# Sheet_2.net
KiCad netlist of a schematic drawn in Altium Designer
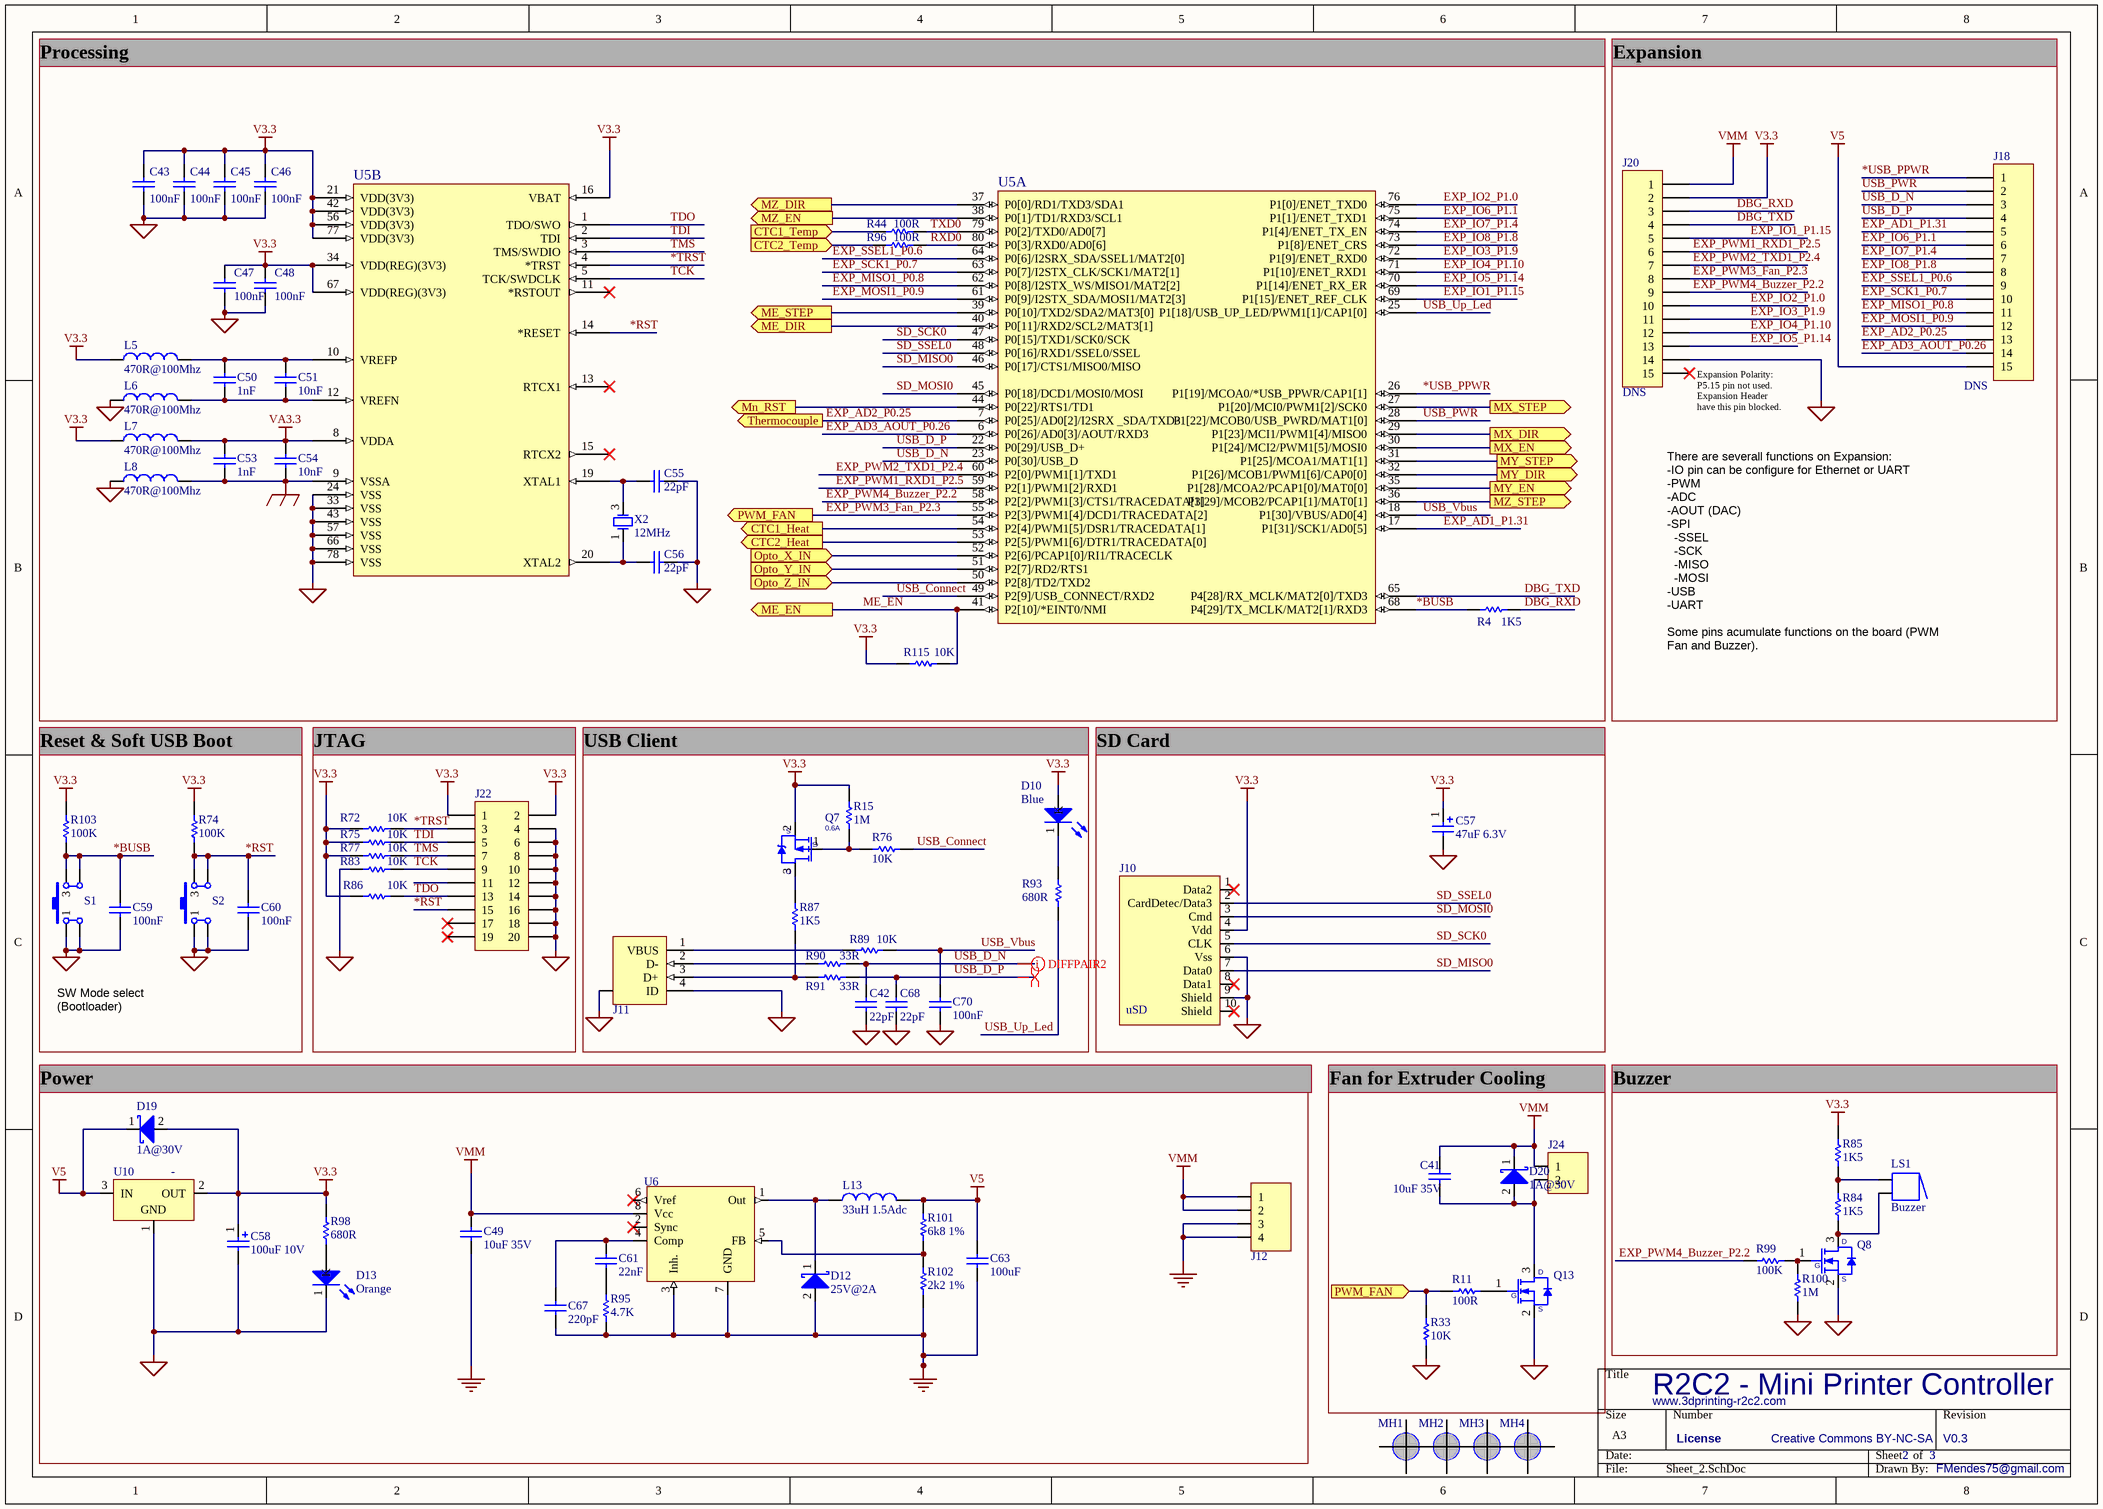
[diagram p0: Sheet_2.SchDoc]

(export (version "E")
  (design (tool "Eeschema 10.0.6"))
  (components
    (comp (ref "C41")
      (value "10uF 35V")
      (footprint "CAPC3216M")
      (description "CAP CER 10UF 35V Y5V 1206")
      (fields (field (name "MANUFACTURER") "Taiyo Yuden"))
      (libsource (lib "HB_DB_Components") (part "Cap Non Pol"))
    )
    (comp (ref "C42")
      (value "22pF")
      (footprint "CAPC1608M")
      (description "CAP CER 22PF 50V 5% NP0 0603")
      (fields (field (name "MANUFACTURER") "TDK"))
      (libsource (lib "HB_DB_Components") (part "Cap Non Pol"))
    )
    (comp (ref "C43")
      (value "100nF")
      (footprint "CAPC1608M")
      (description "CAP CER 0.1UF 50V Y5V 0603")
      (fields (field (name "MANUFACTURER") "Yageo"))
      (libsource (lib "HB_DB_Components") (part "Cap Non Pol"))
    )
    (comp (ref "C44")
      (value "100nF")
      (footprint "CAPC1608M")
      (description "CAP CER 0.1UF 50V Y5V 0603")
      (fields (field (name "MANUFACTURER") "Yageo"))
      (libsource (lib "HB_DB_Components") (part "Cap Non Pol"))
    )
    (comp (ref "C45")
      (value "100nF")
      (footprint "CAPC1608M")
      (description "CAP CER 0.1UF 50V Y5V 0603")
      (fields (field (name "MANUFACTURER") "Yageo"))
      (libsource (lib "HB_DB_Components") (part "Cap Non Pol"))
    )
    (comp (ref "C46")
      (value "100nF")
      (footprint "CAPC1608M")
      (description "CAP CER 0.1UF 50V Y5V 0603")
      (fields (field (name "MANUFACTURER") "Yageo"))
      (libsource (lib "HB_DB_Components") (part "Cap Non Pol"))
    )
    (comp (ref "C47")
      (value "100nF")
      (footprint "CAPC1608M")
      (description "CAP CER 0.1UF 50V Y5V 0603")
      (fields (field (name "MANUFACTURER") "Yageo"))
      (libsource (lib "HB_DB_Components") (part "Cap Non Pol"))
    )
    (comp (ref "C48")
      (value "100nF")
      (footprint "CAPC1608M")
      (description "CAP CER 0.1UF 50V Y5V 0603")
      (fields (field (name "MANUFACTURER") "Yageo"))
      (libsource (lib "HB_DB_Components") (part "Cap Non Pol"))
    )
    (comp (ref "C49")
      (value "10uF 35V")
      (footprint "CAPC3216M")
      (description "CAP CER 10UF 35V Y5V 1206")
      (fields (field (name "MANUFACTURER") "Taiyo Yuden"))
      (libsource (lib "HB_DB_Components") (part "Cap Non Pol"))
    )
    (comp (ref "C50")
      (value "1nF")
      (footprint "CAPC1608M")
      (description "CAP CER 1000PF 50V 10% X7R 0603")
      (fields (field (name "MANUFACTURER") "TDK"))
      (libsource (lib "HB_DB_Components") (part "Cap Non Pol"))
    )
    (comp (ref "C51")
      (value "10nF")
      (footprint "CAPC1608M")
      (description "CAP CER 10000PF 50V 10% X7R 0603")
      (fields (field (name "MANUFACTURER") "TDK"))
      (libsource (lib "HB_DB_Components") (part "Cap Non Pol"))
    )
    (comp (ref "C53")
      (value "1nF")
      (footprint "CAPC1608M")
      (description "CAP CER 1000PF 50V 10% X7R 0603")
      (fields (field (name "MANUFACTURER") "TDK"))
      (libsource (lib "HB_DB_Components") (part "Cap Non Pol"))
    )
    (comp (ref "C54")
      (value "10nF")
      (footprint "CAPC1608M")
      (description "CAP CER 10000PF 50V 10% X7R 0603")
      (fields (field (name "MANUFACTURER") "TDK"))
      (libsource (lib "HB_DB_Components") (part "Cap Non Pol"))
    )
    (comp (ref "C55")
      (value "22pF")
      (footprint "CAPC1608M")
      (description "CAP CER 22PF 50V 5% NP0 0603")
      (fields (field (name "MANUFACTURER") "TDK"))
      (libsource (lib "HB_DB_Components") (part "Cap Non Pol"))
    )
    (comp (ref "C56")
      (value "22pF")
      (footprint "CAPC1608M")
      (description "CAP CER 22PF 50V 5% NP0 0603")
      (fields (field (name "MANUFACTURER") "TDK"))
      (libsource (lib "HB_DB_Components") (part "Cap Non Pol"))
    )
    (comp (ref "C57")
      (value "47uF 6.3V")
      (footprint "Tant_nichicon_B")
      (description "CAP TANT 47UF 6.3V 10% 1411")
      (fields (field (name "MANUFACTURER") "Nichicon"))
      (libsource (lib "HB_DB_Components") (part "Cap Pol"))
    )
    (comp (ref "C58")
      (value "100uF 10V")
      (footprint "CAPAE6666X54M")
      (description "CAP ALUM 100UF 16V 20% SMD")
      (fields (field (name "MANUFACTURER") "Nichicon"))
      (libsource (lib "HB_DB_Components") (part "Cap Pol"))
    )
    (comp (ref "C59")
      (value "100nF")
      (footprint "CAPC1608M")
      (description "CAP CER 0.1UF 50V Y5V 0603")
      (fields (field (name "MANUFACTURER") "Yageo"))
      (libsource (lib "HB_DB_Components") (part "Cap Non Pol"))
    )
    (comp (ref "C60")
      (value "100nF")
      (footprint "CAPC1608M")
      (description "CAP CER 0.1UF 50V Y5V 0603")
      (fields (field (name "MANUFACTURER") "Yageo"))
      (libsource (lib "HB_DB_Components") (part "Cap Non Pol"))
    )
    (comp (ref "C61")
      (value "22nF")
      (footprint "CAPC1608M")
      (description "CAP CER 0.022UF 50V 20% X7R 0603")
      (fields (field (name "MANUFACTURER") "TDK"))
      (libsource (lib "HB_DB_Components") (part "Cap Non Pol"))
    )
    (comp (ref "C63")
      (value "100uF")
      (footprint "CAPC3216M")
      (description "CAP CER 100UF 10V 20% X5R 1206")
      (fields (field (name "MANUFACTURER") "TDK"))
      (libsource (lib "HB_DB_Components") (part "Cap Non Pol"))
    )
    (comp (ref "C67")
      (value "220pF")
      (footprint "CAPC1608M")
      (description "CAP CER 220PF 50V 5% NP0 0603")
      (fields (field (name "MANUFACTURER") "TDK"))
      (libsource (lib "HB_DB_Components") (part "Cap Non Pol"))
    )
    (comp (ref "C68")
      (value "22pF")
      (footprint "CAPC1608M")
      (description "CAP CER 22PF 50V 5% NP0 0603")
      (fields (field (name "MANUFACTURER") "TDK"))
      (libsource (lib "HB_DB_Components") (part "Cap Non Pol"))
    )
    (comp (ref "C70")
      (value "100nF")
      (footprint "CAPC1608M")
      (description "CAP CER 0.1UF 50V Y5V 0603")
      (fields (field (name "MANUFACTURER") "Yageo"))
      (libsource (lib "HB_DB_Components") (part "Cap Non Pol"))
    )
    (comp (ref "D10")
      (value "Blue")
      (footprint "LEDM_3216X12M")
      (description "LED BLUE CLEAR 1206 REV MT SMD")
      (fields (field (name "MANUFACTURER") "Lite-On Inc"))
      (libsource (lib "HB_DB_Components") (part "LED"))
    )
    (comp (ref "D12")
      (value "25V@2A")
      (footprint "SMB")
      (description "DIODE SCHOTTKY 25V 2A SMB")
      (fields (field (name "MANUFACTURER") "STMicroelectronics"))
      (libsource (lib "HB_DB_Components") (part "D Schottky"))
    )
    (comp (ref "D13")
      (value "Orange")
      (footprint "LEDM_3216X12M")
      (description "LED 3.2X1.6MM 601NM ORN CLR SMD")
      (fields (field (name "MANUFACTURER") "OSRAM"))
      (libsource (lib "HB_DB_Components") (part "LED"))
    )
    (comp (ref "D19")
      (value "1A@30V")
      (footprint "SOD323")
      (description "DIODE SCHOTTKY 30V 1A SOD323F")
      (fields (field (name "MANUFACTURER") "NXP"))
      (libsource (lib "HB_DB_Components") (part "D Schottky"))
    )
    (comp (ref "D20")
      (value "1A@30V")
      (footprint "SOD323")
      (description "DIODE SCHOTTKY 30V 1A SOD323F")
      (fields (field (name "MANUFACTURER") "NXP"))
      (libsource (lib "HB_DB_Components") (part "D Schottky"))
    )
    (comp (ref "J10")
      (value "uSD")
      (footprint "3M_2900")
      (description "CONN MINI MICRO-SD 8PIN PCB GOLD")
      (fields (field (name "MANUFACTURER") "Amphenol"))
      (libsource (lib "HB_DB_Components") (part "Con uSD"))
    )
    (comp (ref "J11")
      (value "micro-usb")
      (footprint "USB_47589-001")
      (description "CONN RCPT MICRO USB AB R/A SMD")
      (fields (field (name "MANUFACTURER") "Molex Inc"))
      (libsource (lib "HB") (part "Con 4 USB"))
    )
    (comp (ref "J12")
      (value "~")
      (footprint "TE_SCREW_282841-4")
      (description "Con 4")
      (fields (field (name "MANUFACTURER") "TE"))
      (libsource (lib "HB_DB_Components") (part "Con 4"))
    )
    (comp (ref "J18")
      (value "~")
      (footprint "HDR1X15")
      (description "15 SIL VERT PIN HDR")
      (fields (field (name "POPULATE") "DNS") (field (name "MANUFACTURER") "Harwin Inc"))
      (libsource (lib "HB_DB_Components") (part "Con 15"))
    )
    (comp (ref "J20")
      (value "~")
      (footprint "HDR1X15")
      (description "15 SIL VERT PIN HDR")
      (fields (field (name "POPULATE") "DNS") (field (name "MANUFACTURER") "Harwin Inc"))
      (libsource (lib "") (part "Con 15_1"))
    )
    (comp (ref "J22")
      (value "~")
      (footprint "HDR2X10")
      (description "Headers & Wire Housings 2 X 10 SHROUDED HDR")
      (fields (field (name "MANUFACTURER") "Molex"))
      (libsource (lib "HB_DB_Components") (part "Con 10X2"))
    )
    (comp (ref "J24")
      (value "-")
      (footprint "MOLEX_22-29-2021")
      (description "CONN HEADER 2POS .100 VERT GOLD")
      (fields (field (name "MANUFACTURER") "Molex"))
      (libsource (lib "HB_DB_Components") (part "Con 2"))
    )
    (comp (ref "L5")
      (value "470R@100Mhz")
      (footprint "INDC1608M")
      (description "FERRITE CHIP 470 OHM 1000MA 0603")
      (fields (field (name "MANUFACTURER") "MURATA"))
      (libsource (lib "HB_DB_Components") (part "Ind"))
    )
    (comp (ref "L6")
      (value "470R@100Mhz")
      (footprint "INDC1608M")
      (description "FERRITE CHIP 470 OHM 1000MA 0603")
      (fields (field (name "MANUFACTURER") "MURATA"))
      (libsource (lib "HB_DB_Components") (part "Ind"))
    )
    (comp (ref "L7")
      (value "470R@100Mhz")
      (footprint "INDC1608M")
      (description "FERRITE CHIP 470 OHM 1000MA 0603")
      (fields (field (name "MANUFACTURER") "MURATA"))
      (libsource (lib "HB_DB_Components") (part "Ind"))
    )
    (comp (ref "L8")
      (value "470R@100Mhz")
      (footprint "INDC1608M")
      (description "FERRITE CHIP 470 OHM 1000MA 0603")
      (fields (field (name "MANUFACTURER") "MURATA"))
      (libsource (lib "HB_DB_Components") (part "Ind"))
    )
    (comp (ref "L13")
      (value "33uH 1.5Adc")
      (footprint "INDP6x6")
      (description "INDUCTOR 33UH 1.4A 20% SMD")
      (fields (field (name "MANUFACTURER") "Taiyo Yuden"))
      (libsource (lib "HB_DB_Components") (part "Ind"))
    )
    (comp (ref "LS1")
      (value "Buzzer")
      (footprint "TDK_PS1240")
      (description "BUZZER PIEZO 4KHZ 12.2MM PC MNT")
      (fields (field (name "MANUFACTURER") "TDK"))
      (libsource (lib "HB_DB_Components") (part "Buzzer"))
    )
    (comp (ref "MH1")
      (value "-")
      (footprint "MH_M3")
      (description "MH")
      (libsource (lib "HB_DB_Components") (part "MH"))
    )
    (comp (ref "MH2")
      (value "-")
      (footprint "MH_M3")
      (description "MH")
      (libsource (lib "HB_DB_Components") (part "MH"))
    )
    (comp (ref "MH3")
      (value "-")
      (footprint "MH_M3")
      (description "MH")
      (libsource (lib "HB_DB_Components") (part "MH"))
    )
    (comp (ref "MH4")
      (value "-")
      (footprint "MH_M3")
      (description "MH")
      (libsource (lib "HB_DB_Components") (part "MH"))
    )
    (comp (ref "Q7")
      (value "0.6A")
      (footprint "SOT23-3M")
      (description "MOSFET P-CH 30V 760MA SOT-23")
      (fields (field (name "MANUFACTURER") "International Rectifier"))
      (libsource (lib "HB_DB_Components") (part "MOS-P"))
    )
    (comp (ref "Q8")
      (value "~")
      (footprint "SOT323-3AM")
      (description "MOSFET N-CH SGL 60V SOT-323")
      (fields (field (name "MANUFACTURER") "NXP"))
      (libsource (lib "HB_DB_Components") (part "Q MOSFET-N"))
    )
    (comp (ref "Q13")
      (value "~")
      (footprint "SOT323-3AM")
      (description "MOSFET N-CH SGL 60V SOT-323")
      (fields (field (name "MANUFACTURER") "NXP"))
      (libsource (lib "HB_DB_Components") (part "Q MOSFET-N"))
    )
    (comp (ref "R4")
      (value "1K5")
      (footprint "RESC1608M")
      (description "RES 1.5K OHM 1/10W 5% 0603")
      (fields (field (name "MANUFACTURER") "Stackpole Electronics Inc"))
      (libsource (lib "HB_DB_Components") (part "Res"))
    )
    (comp (ref "R11")
      (value "100R")
      (footprint "RESC1608M")
      (description "RES 100 OHM 1/10W 5% 0603")
      (fields (field (name "MANUFACTURER") "Stackpole Electronics Inc"))
      (libsource (lib "HB_DB_Components") (part "Res"))
    )
    (comp (ref "R15")
      (value "1M")
      (footprint "RESC1608M")
      (description "RES 1M OHM 1/10W 1% 0603")
      (fields (field (name "MANUFACTURER") "Stackpole Electronics Inc"))
      (libsource (lib "HB_DB_Components") (part "Res"))
    )
    (comp (ref "R33")
      (value "10K")
      (footprint "RESC1608M")
      (description "RES 10K OHM 1/10W 5% 0603 SMD")
      (fields (field (name "MANUFACTURER") "Yageo"))
      (libsource (lib "HB_DB_Components") (part "Res"))
    )
    (comp (ref "R44")
      (value "100R")
      (footprint "RESC1608M")
      (description "RES 100 OHM 1/10W 5% 0603")
      (fields (field (name "MANUFACTURER") "Stackpole Electronics Inc"))
      (libsource (lib "HB_DB_Components") (part "Res"))
    )
    (comp (ref "R72")
      (value "10K")
      (footprint "RESC1608M")
      (description "RES 10K OHM 1/10W 5% 0603 SMD")
      (fields (field (name "MANUFACTURER") "Yageo"))
      (libsource (lib "HB_DB_Components") (part "Res"))
    )
    (comp (ref "R74")
      (value "100K")
      (footprint "RESC1608M")
      (description "RES 100K OHM 1/10W 5% 0603 SMD")
      (fields (field (name "MANUFACTURER") "Yageo"))
      (libsource (lib "HB_DB_Components") (part "Res"))
    )
    (comp (ref "R75")
      (value "10K")
      (footprint "RESC1608M")
      (description "RES 10K OHM 1/10W 5% 0603 SMD")
      (fields (field (name "MANUFACTURER") "Yageo"))
      (libsource (lib "HB_DB_Components") (part "Res"))
    )
    (comp (ref "R76")
      (value "10K")
      (footprint "RESC1608M")
      (description "RES 10K OHM 1/10W 5% 0603 SMD")
      (fields (field (name "MANUFACTURER") "Yageo"))
      (libsource (lib "HB_DB_Components") (part "Res"))
    )
    (comp (ref "R77")
      (value "10K")
      (footprint "RESC1608M")
      (description "RES 10K OHM 1/10W 5% 0603 SMD")
      (fields (field (name "MANUFACTURER") "Yageo"))
      (libsource (lib "HB_DB_Components") (part "Res"))
    )
    (comp (ref "R83")
      (value "10K")
      (footprint "RESC1608M")
      (description "RES 10K OHM 1/10W 5% 0603 SMD")
      (fields (field (name "MANUFACTURER") "Yageo"))
      (libsource (lib "HB_DB_Components") (part "Res"))
    )
    (comp (ref "R84")
      (value "1K5")
      (footprint "RESC1608M")
      (description "RES 1.5K OHM 1/10W 5% 0603")
      (fields (field (name "MANUFACTURER") "Stackpole Electronics Inc"))
      (libsource (lib "HB_DB_Components") (part "Res"))
    )
    (comp (ref "R85")
      (value "1K5")
      (footprint "RESC1608M")
      (description "RES 1.5K OHM 1/10W 5% 0603")
      (fields (field (name "MANUFACTURER") "Stackpole Electronics Inc"))
      (libsource (lib "HB_DB_Components") (part "Res"))
    )
    (comp (ref "R86")
      (value "10K")
      (footprint "RESC1608M")
      (description "RES 10K OHM 1/10W 5% 0603 SMD")
      (fields (field (name "MANUFACTURER") "Yageo"))
      (libsource (lib "HB_DB_Components") (part "Res"))
    )
    (comp (ref "R87")
      (value "1K5")
      (footprint "RESC1608M")
      (description "RES 1.5K OHM 1/10W 5% 0603")
      (fields (field (name "MANUFACTURER") "Stackpole Electronics Inc"))
      (libsource (lib "HB_DB_Components") (part "Res"))
    )
    (comp (ref "R89")
      (value "10K")
      (footprint "RESC1608M")
      (description "RES 10K OHM 1/10W 5% 0603 SMD")
      (fields (field (name "MANUFACTURER") "Yageo"))
      (libsource (lib "HB_DB_Components") (part "Res"))
    )
    (comp (ref "R90")
      (value "33R")
      (footprint "RESC1608M")
      (description "RES 33 OHM 1/10W 1% 0603")
      (fields (field (name "MANUFACTURER") "Stackpole Electronics Inc"))
      (libsource (lib "HB_DB_Components") (part "Res"))
    )
    (comp (ref "R91")
      (value "33R")
      (footprint "RESC1608M")
      (description "RES 33 OHM 1/10W 1% 0603")
      (fields (field (name "MANUFACTURER") "Stackpole Electronics Inc"))
      (libsource (lib "HB_DB_Components") (part "Res"))
    )
    (comp (ref "R93")
      (value "680R")
      (footprint "RESC1608M")
      (description "RES 680 OHM 1/10W 1% 0603 SMD")
      (fields (field (name "MANUFACTURER") "Panasonic"))
      (libsource (lib "HB_DB_Components") (part "Res"))
    )
    (comp (ref "R95")
      (value "4.7K")
      (footprint "CAPC1608M")
      (description "4K7")
      (fields (field (name "MANUFACTURER") "Multicomp"))
      (libsource (lib "HB_DB_Components") (part "Res"))
    )
    (comp (ref "R96")
      (value "100R")
      (footprint "RESC1608M")
      (description "RES 100 OHM 1/10W 5% 0603")
      (fields (field (name "MANUFACTURER") "Stackpole Electronics Inc"))
      (libsource (lib "HB_DB_Components") (part "Res"))
    )
    (comp (ref "R98")
      (value "680R")
      (footprint "RESC1608M")
      (description "RES 680 OHM 1/10W 1% 0603 SMD")
      (fields (field (name "MANUFACTURER") "Panasonic"))
      (libsource (lib "HB_DB_Components") (part "Res"))
    )
    (comp (ref "R99")
      (value "100K")
      (footprint "RESC1608M")
      (description "RES 100K OHM 1/10W 5% 0603 SMD")
      (fields (field (name "MANUFACTURER") "Yageo"))
      (libsource (lib "HB_DB_Components") (part "Res"))
    )
    (comp (ref "R100")
      (value "1M")
      (footprint "RESC1608M")
      (description "RES 1M OHM 1/10W 1% 0603")
      (fields (field (name "MANUFACTURER") "Stackpole Electronics Inc"))
      (libsource (lib "HB_DB_Components") (part "Res"))
    )
    (comp (ref "R101")
      (value "6k8 1%")
      (footprint "RESC1608M")
      (description "RES 6.8K OHM 1/10W 1% 0603")
      (fields (field (name "MANUFACTURER") "Stackpole Electronics Inc"))
      (libsource (lib "HB_DB_Components") (part "Res"))
    )
    (comp (ref "R102")
      (value "2k2 1%")
      (footprint "RESC1608M")
      (description "RES 2.2K OHM 1/10W .1% 0603 SMD")
      (fields (field (name "MANUFACTURER") "Panasonic"))
      (libsource (lib "HB_DB_Components") (part "Res"))
    )
    (comp (ref "R103")
      (value "100K")
      (footprint "RESC1608M")
      (description "RES 100K OHM 1/10W 5% 0603 SMD")
      (fields (field (name "MANUFACTURER") "Yageo"))
      (libsource (lib "HB_DB_Components") (part "Res"))
    )
    (comp (ref "R115")
      (value "10K")
      (footprint "RESC1608M")
      (description "RES 10K OHM 1/10W 5% 0603 SMD")
      (fields (field (name "MANUFACTURER") "Yageo"))
      (libsource (lib "HB_DB_Components") (part "Res"))
    )
    (comp (ref "S1")
      (value "SW-PB")
      (footprint "SW_FSM6JSMA")
      (description "SWITCH TACTILE SPST-NO 0.05A 12V")
      (fields (field (name "MANUFACTURER") "TE Connectivity"))
      (libsource (lib "HB_DB_Components") (part "SW-PB"))
    )
    (comp (ref "S2")
      (value "SW-PB")
      (footprint "SW_FSM6JSMA")
      (description "SWITCH TACTILE SPST-NO 0.05A 12V")
      (fields (field (name "MANUFACTURER") "TE Connectivity"))
      (libsource (lib "HB_DB_Components") (part "SW-PB"))
    )
    (comp (ref "U5")
      (value "~")
      (footprint "TSQFP50P1400X1400X160-80M")
      (description "IC ARM CORTEX MCU 512K 80-LQFP")
      (fields (field (name "MANUFACTURER") "NXP"))
      (libsource (lib "HB_DB_Components") (part "IC LPC175x"))
    )
    (comp (ref "U6")
      (value "~")
      (footprint "SOIC127P600-8M")
      (description "IC REG BUCK ADJ 1A 8SOIC")
      (fields (field (name "MANUFACTURER") "STMicroelectronics"))
      (libsource (lib "HB_DB_Components") (part "IC L5970D"))
    )
    (comp (ref "U10")
      (value "-")
      (footprint "SOT223-4M")
      (description "IC REG LDO 3.3V 0.8A SOT223")
      (fields (field (name "MANUFACTURER") "Texas Instruments"))
      (libsource (lib "HB_DB_Components") (part "IC_TLV1117-3.3"))
    )
    (comp (ref "X2")
      (value "12MHz")
      (footprint "txc_7b_12MHZ")
      (description "CRYSTAL 12.000MHZ 18PF SMD")
      (fields (field (name "MANUFACTURER") "TXC CORPORATION"))
      (libsource (lib "HB_DB_Components") (part "XTAL"))
    )
  )
  (nets
    (net (code "1") (name "/*BUSB") (class "Default")
      (node (ref "C59") (pin "2") (pinfunction "2_2") (pintype "passive"))
      (node (ref "R103") (pin "1") (pinfunction "1_1") (pintype "passive"))
      (node (ref "R4") (pin "1") (pinfunction "1_1") (pintype "passive"))
      (node (ref "S1") (pin "3") (pinfunction "3_3") (pintype "passive"))
      (node (ref "S1") (pin "4") (pinfunction "4_4") (pintype "passive"))
      (node (ref "U5") (pin "68") (pinfunction "P4[29]/TX_MCLK/MAT2[1]/RXD3_68") (pintype "bidirectional"))
    )
    (net (code "2") (name "/*RST") (class "Default")
      (node (ref "C60") (pin "2") (pinfunction "2_2") (pintype "passive"))
      (node (ref "J22") (pin "15") (pinfunction "15_15") (pintype "passive"))
      (node (ref "R74") (pin "1") (pinfunction "1_1") (pintype "passive"))
      (node (ref "S2") (pin "3") (pinfunction "3_3") (pintype "passive"))
      (node (ref "S2") (pin "4") (pinfunction "4_4") (pintype "passive"))
      (node (ref "U5") (pin "14") (pinfunction "*RESET_14") (pintype "input"))
    )
    (net (code "3") (name "/*TRST") (class "Default")
      (node (ref "J22") (pin "3") (pinfunction "3_3") (pintype "passive"))
      (node (ref "R72") (pin "2") (pinfunction "2_2") (pintype "passive"))
      (node (ref "U5") (pin "4") (pinfunction "*TRST_4") (pintype "input"))
    )
    (net (code "4") (name "/*USB_PPWR") (class "Default")
      (node (ref "J18") (pin "1") (pinfunction "1_1") (pintype "passive"))
      (node (ref "U5") (pin "26") (pinfunction "P1[19]/MCOA0/*USB_PPWR/CAP1[1]_26") (pintype "bidirectional"))
    )
    (net (code "5") (name "/CTC1_Heat") (class "Default")
      (node (ref "U5") (pin "54") (pinfunction "P2[4]/PWM1[5]/DSR1/TRACEDATA[1]_54") (pintype "bidirectional"))
    )
    (net (code "6") (name "/CTC1_Temp") (class "Default")
      (node (ref "R44") (pin "1") (pinfunction "1_1") (pintype "passive"))
    )
    (net (code "7") (name "/CTC2_Heat") (class "Default")
      (node (ref "U5") (pin "53") (pinfunction "P2[5]/PWM1[6]/DTR1/TRACEDATA[0]_53") (pintype "bidirectional"))
    )
    (net (code "8") (name "/CTC2_Temp") (class "Default")
      (node (ref "R96") (pin "1") (pinfunction "1_1") (pintype "passive"))
    )
    (net (code "9") (name "/DBG_RXD") (class "Default")
      (node (ref "J20") (pin "3") (pinfunction "3_3") (pintype "passive"))
      (node (ref "R4") (pin "2") (pinfunction "2_2") (pintype "passive"))
    )
    (net (code "10") (name "/DBG_TXD") (class "Default")
      (node (ref "J20") (pin "4") (pinfunction "4_4") (pintype "passive"))
      (node (ref "U5") (pin "65") (pinfunction "P4[28]/RX_MCLK/MAT2[0]/TXD3_65") (pintype "bidirectional"))
    )
    (net (code "11") (name "/EXP_AD1_P1.31") (class "Default")
      (node (ref "J18") (pin "5") (pinfunction "5_5") (pintype "passive"))
      (node (ref "U5") (pin "17") (pinfunction "P1[31]/SCK1/AD0[5]_17") (pintype "bidirectional"))
    )
    (net (code "12") (name "/EXP_AD2_P0.25") (class "Default")
      (node (ref "J18") (pin "13") (pinfunction "13_13") (pintype "passive"))
      (node (ref "U5") (pin "7") (pinfunction "P0[25]/AD0[2]/I2SRX__SDA/TXD3_7") (pintype "bidirectional"))
    )
    (net (code "13") (name "/EXP_AD3_AOUT_P0.26") (class "Default")
      (node (ref "J18") (pin "14") (pinfunction "14_14") (pintype "passive"))
      (node (ref "U5") (pin "6") (pinfunction "P0[26]/AD0[3]/AOUT/RXD3_6") (pintype "bidirectional"))
    )
    (net (code "14") (name "/EXP_IO1_P1.15") (class "Default")
      (node (ref "J20") (pin "5") (pinfunction "5_5") (pintype "passive"))
      (node (ref "U5") (pin "69") (pinfunction "P1[15]/ENET_REF_CLK_69") (pintype "bidirectional"))
    )
    (net (code "15") (name "/EXP_IO2_P1.0") (class "Default")
      (node (ref "J20") (pin "10") (pinfunction "10_10") (pintype "passive"))
      (node (ref "U5") (pin "76") (pinfunction "P1[0]/ENET_TXD0_76") (pintype "bidirectional"))
    )
    (net (code "16") (name "/EXP_IO3_P1.9") (class "Default")
      (node (ref "J20") (pin "11") (pinfunction "11_11") (pintype "passive"))
      (node (ref "U5") (pin "72") (pinfunction "P1[9]/ENET_RXD0_72") (pintype "bidirectional"))
    )
    (net (code "17") (name "/EXP_IO4_P1.10") (class "Default")
      (node (ref "J20") (pin "12") (pinfunction "12_12") (pintype "passive"))
      (node (ref "U5") (pin "71") (pinfunction "P1[10]/ENET_RXD1_71") (pintype "bidirectional"))
    )
    (net (code "18") (name "/EXP_IO5_P1.14") (class "Default")
      (node (ref "J20") (pin "13") (pinfunction "13_13") (pintype "passive"))
      (node (ref "U5") (pin "70") (pinfunction "P1[14]/ENET_RX_ER_70") (pintype "bidirectional"))
    )
    (net (code "19") (name "/EXP_IO6_P1.1") (class "Default")
      (node (ref "J18") (pin "6") (pinfunction "6_6") (pintype "passive"))
      (node (ref "U5") (pin "75") (pinfunction "P1[1]/ENET_TXD1_75") (pintype "bidirectional"))
    )
    (net (code "20") (name "/EXP_IO7_P1.4") (class "Default")
      (node (ref "J18") (pin "7") (pinfunction "7_7") (pintype "passive"))
      (node (ref "U5") (pin "74") (pinfunction "P1[4]/ENET_TX_EN_74") (pintype "bidirectional"))
    )
    (net (code "21") (name "/EXP_IO8_P1.8") (class "Default")
      (node (ref "J18") (pin "8") (pinfunction "8_8") (pintype "passive"))
      (node (ref "U5") (pin "73") (pinfunction "P1[8]/ENET_CRS_73") (pintype "bidirectional"))
    )
    (net (code "22") (name "/EXP_MISO1_P0.8") (class "Default")
      (node (ref "J18") (pin "11") (pinfunction "11_11") (pintype "passive"))
      (node (ref "U5") (pin "62") (pinfunction "P0[8]/I2STX_WS/MISO1/MAT2[2]_62") (pintype "bidirectional"))
    )
    (net (code "23") (name "/EXP_MOSI1_P0.9") (class "Default")
      (node (ref "J18") (pin "12") (pinfunction "12_12") (pintype "passive"))
      (node (ref "U5") (pin "61") (pinfunction "P0[9]/I2STX_SDA/MOSI1/MAT2[3]_61") (pintype "bidirectional"))
    )
    (net (code "24") (name "/EXP_PWM1_RXD1_P2.5") (class "Default")
      (node (ref "J20") (pin "6") (pinfunction "6_6") (pintype "passive"))
      (node (ref "U5") (pin "59") (pinfunction "P2[1]/PWM1[2]/RXD1_59") (pintype "bidirectional"))
    )
    (net (code "25") (name "/EXP_PWM2_TXD1_P2.4") (class "Default")
      (node (ref "J20") (pin "7") (pinfunction "7_7") (pintype "passive"))
      (node (ref "U5") (pin "60") (pinfunction "P2[0]/PWM1[1]/TXD1_60") (pintype "bidirectional"))
    )
    (net (code "26") (name "/EXP_PWM3_Fan_P2.3") (class "Default")
      (node (ref "J20") (pin "8") (pinfunction "8_8") (pintype "passive"))
      (node (ref "R11") (pin "1") (pinfunction "1_1") (pintype "passive"))
      (node (ref "R33") (pin "2") (pinfunction "2_2") (pintype "passive"))
      (node (ref "U5") (pin "55") (pinfunction "P2[3]/PWM1[4]/DCD1/TRACEDATA[2]_55") (pintype "bidirectional"))
    )
    (net (code "27") (name "/EXP_PWM4_Buzzer_P2.2") (class "Default")
      (node (ref "J20") (pin "9") (pinfunction "9_9") (pintype "passive"))
      (node (ref "R99") (pin "1") (pinfunction "1_1") (pintype "passive"))
      (node (ref "U5") (pin "58") (pinfunction "P2[2]/PWM1[3]/CTS1/TRACEDATA[3]_58") (pintype "bidirectional"))
    )
    (net (code "28") (name "/EXP_SCK1_P0.7") (class "Default")
      (node (ref "J18") (pin "10") (pinfunction "10_10") (pintype "passive"))
      (node (ref "U5") (pin "63") (pinfunction "P0[7]/I2STX_CLK/SCK1/MAT2[1]_63") (pintype "bidirectional"))
    )
    (net (code "29") (name "/EXP_SSEL1_P0.6") (class "Default")
      (node (ref "J18") (pin "9") (pinfunction "9_9") (pintype "passive"))
      (node (ref "U5") (pin "64") (pinfunction "P0[6]/I2SRX_SDA/SSEL1/MAT2[0]_64") (pintype "bidirectional"))
    )
    (net (code "30") (name "/ME_DIR") (class "Default")
      (node (ref "U5") (pin "40") (pinfunction "P0[11]/RXD2/SCL2/MAT3[1]_40") (pintype "bidirectional"))
    )
    (net (code "31") (name "/ME_EN") (class "Default")
      (node (ref "R115") (pin "2") (pinfunction "2_2") (pintype "passive"))
      (node (ref "U5") (pin "41") (pinfunction "P2[10]/*EINT0/NMI_41") (pintype "bidirectional"))
    )
    (net (code "32") (name "/ME_STEP") (class "Default")
      (node (ref "U5") (pin "39") (pinfunction "P0[10]/TXD2/SDA2/MAT3[0]_39") (pintype "bidirectional"))
    )
    (net (code "33") (name "/MX_DIR") (class "Default")
      (node (ref "U5") (pin "29") (pinfunction "P1[23]/MCI1/PWM1[4]/MISO0_29") (pintype "bidirectional"))
    )
    (net (code "34") (name "/MX_EN") (class "Default")
      (node (ref "U5") (pin "30") (pinfunction "P1[24]/MCI2/PWM1[5]/MOSI0_30") (pintype "bidirectional"))
    )
    (net (code "35") (name "/MX_STEP") (class "Default")
      (node (ref "U5") (pin "27") (pinfunction "P1[20]/MCI0/PWM1[2]/SCK0_27") (pintype "bidirectional"))
    )
    (net (code "36") (name "/MY_DIR") (class "Default")
      (node (ref "U5") (pin "32") (pinfunction "P1[26]/MCOB1/PWM1[6]/CAP0[0]_32") (pintype "bidirectional"))
    )
    (net (code "37") (name "/MY_EN") (class "Default")
      (node (ref "U5") (pin "35") (pinfunction "P1[28]/MCOA2/PCAP1[0]/MAT0[0]_35") (pintype "bidirectional"))
    )
    (net (code "38") (name "/MY_STEP") (class "Default")
      (node (ref "U5") (pin "31") (pinfunction "P1[25]/MCOA1/MAT1[1]_31") (pintype "bidirectional"))
    )
    (net (code "39") (name "/MZ_DIR") (class "Default")
      (node (ref "U5") (pin "37") (pinfunction "P0[0]/RD1/TXD3/SDA1_37") (pintype "bidirectional"))
    )
    (net (code "40") (name "/MZ_EN") (class "Default")
      (node (ref "U5") (pin "38") (pinfunction "P0[1]/TD1/RXD3/SCL1_38") (pintype "bidirectional"))
    )
    (net (code "41") (name "/MZ_STEP") (class "Default")
      (node (ref "U5") (pin "36") (pinfunction "P1[29]/MCOB2/PCAP1[1]/MAT0[1]_36") (pintype "bidirectional"))
    )
    (net (code "42") (name "/Mn_RST") (class "Default")
      (node (ref "U5") (pin "44") (pinfunction "P0[22]/RTS1/TD1_44") (pintype "bidirectional"))
    )
    (net (code "43") (name "/Opto_X_IN") (class "Default")
      (node (ref "U5") (pin "52") (pinfunction "P2[6]/PCAP1[0]/RI1/TRACECLK_52") (pintype "bidirectional"))
    )
    (net (code "44") (name "/Opto_Y_IN") (class "Default")
      (node (ref "U5") (pin "51") (pinfunction "P2[7]/RD2/RTS1_51") (pintype "bidirectional"))
    )
    (net (code "45") (name "/Opto_Z_IN") (class "Default")
      (node (ref "U5") (pin "50") (pinfunction "P2[8]/TD2/TXD2_50") (pintype "bidirectional"))
    )
    (net (code "46") (name "/RXD0") (class "Default")
      (node (ref "R96") (pin "2") (pinfunction "2_2") (pintype "passive"))
      (node (ref "U5") (pin "80") (pinfunction "P0[3]/RXD0/AD0[6]_80") (pintype "bidirectional"))
    )
    (net (code "47") (name "/SD_MISO0") (class "Default")
      (node (ref "J10") (pin "7") (pinfunction "Data0_7") (pintype "passive"))
      (node (ref "U5") (pin "46") (pinfunction "P0[17]/CTS1/MISO0/MISO_46") (pintype "bidirectional"))
    )
    (net (code "48") (name "/SD_MOSI0") (class "Default")
      (node (ref "J10") (pin "3") (pinfunction "Cmd_3") (pintype "passive"))
      (node (ref "U5") (pin "45") (pinfunction "P0[18]/DCD1/MOSI0/MOSI_45") (pintype "bidirectional"))
    )
    (net (code "49") (name "/SD_SCK0") (class "Default")
      (node (ref "J10") (pin "5") (pinfunction "CLK_5") (pintype "passive"))
      (node (ref "U5") (pin "47") (pinfunction "P0[15]/TXD1/SCK0/SCK_47") (pintype "bidirectional"))
    )
    (net (code "50") (name "/SD_SSEL0") (class "Default")
      (node (ref "J10") (pin "2") (pinfunction "CardDetec/Data3_2") (pintype "passive"))
      (node (ref "U5") (pin "48") (pinfunction "P0[16]/RXD1/SSEL0/SSEL_48") (pintype "bidirectional"))
    )
    (net (code "51") (name "/TCK") (class "Default")
      (node (ref "J22") (pin "9") (pinfunction "9_9") (pintype "passive"))
      (node (ref "R83") (pin "2") (pinfunction "2_2") (pintype "passive"))
      (node (ref "U5") (pin "5") (pinfunction "TCK/SWDCLK_5") (pintype "input"))
    )
    (net (code "52") (name "/TDI") (class "Default")
      (node (ref "J22") (pin "5") (pinfunction "5_5") (pintype "passive"))
      (node (ref "R75") (pin "2") (pinfunction "2_2") (pintype "passive"))
      (node (ref "U5") (pin "2") (pinfunction "TDI_2") (pintype "input"))
    )
    (net (code "53") (name "/TDO") (class "Default")
      (node (ref "J22") (pin "13") (pinfunction "13_13") (pintype "passive"))
      (node (ref "R86") (pin "2") (pinfunction "2_2") (pintype "passive"))
      (node (ref "U5") (pin "1") (pinfunction "TDO/SWO_1") (pintype "output"))
    )
    (net (code "54") (name "/TMS") (class "Default")
      (node (ref "J22") (pin "7") (pinfunction "7_7") (pintype "passive"))
      (node (ref "R77") (pin "2") (pinfunction "2_2") (pintype "passive"))
      (node (ref "U5") (pin "3") (pinfunction "TMS/SWDIO_3") (pintype "input"))
    )
    (net (code "55") (name "/TXD0") (class "Default")
      (node (ref "R44") (pin "2") (pinfunction "2_2") (pintype "passive"))
      (node (ref "U5") (pin "79") (pinfunction "P0[2]/TXD0/AD0[7]_79") (pintype "bidirectional"))
    )
    (net (code "56") (name "/USB_Connect") (class "Default")
      (node (ref "R76") (pin "2") (pinfunction "2_2") (pintype "passive"))
      (node (ref "U5") (pin "49") (pinfunction "P2[9]/USB_CONNECT/RXD2_49") (pintype "bidirectional"))
    )
    (net (code "57") (name "/USB_D_N") (class "Default")
      (node (ref "C42") (pin "2") (pinfunction "2_2") (pintype "passive"))
      (node (ref "J18") (pin "3") (pinfunction "3_3") (pintype "passive"))
      (node (ref "R90") (pin "2") (pinfunction "2_2") (pintype "passive"))
      (node (ref "U5") (pin "23") (pinfunction "P0[30]/USB_D_23") (pintype "bidirectional"))
    )
    (net (code "58") (name "/USB_D_P") (class "Default")
      (node (ref "C68") (pin "2") (pinfunction "2_2") (pintype "passive"))
      (node (ref "J18") (pin "4") (pinfunction "4_4") (pintype "passive"))
      (node (ref "R91") (pin "2") (pinfunction "2_2") (pintype "passive"))
      (node (ref "U5") (pin "22") (pinfunction "P0[29]/USB_D+_22") (pintype "bidirectional"))
    )
    (net (code "59") (name "/USB_PWR") (class "Default")
      (node (ref "J18") (pin "2") (pinfunction "2_2") (pintype "passive"))
      (node (ref "U5") (pin "28") (pinfunction "P1[22]/MCOB0/USB_PWRD/MAT1[0]_28") (pintype "bidirectional"))
    )
    (net (code "60") (name "/USB_Up_Led") (class "Default")
      (node (ref "R93") (pin "1") (pinfunction "1_1") (pintype "passive"))
      (node (ref "U5") (pin "25") (pinfunction "P1[18]/USB_UP_LED/PWM1[1]/CAP1[0]_25") (pintype "bidirectional"))
    )
    (net (code "61") (name "/USB_Vbus") (class "Default")
      (node (ref "C70") (pin "2") (pinfunction "2_2") (pintype "passive"))
      (node (ref "R89") (pin "2") (pinfunction "2_2") (pintype "passive"))
      (node (ref "U5") (pin "18") (pinfunction "P1[30]/VBUS/AD0[4]_18") (pintype "bidirectional"))
    )
    (net (code "62") (name "GND") (class "Default")
      (node (ref "C42") (pin "1") (pinfunction "1_1") (pintype "passive"))
      (node (ref "C43") (pin "1") (pinfunction "1_1") (pintype "passive"))
      (node (ref "C44") (pin "1") (pinfunction "1_1") (pintype "passive"))
      (node (ref "C45") (pin "2") (pinfunction "2_2") (pintype "passive"))
      (node (ref "C46") (pin "2") (pinfunction "2_2") (pintype "passive"))
      (node (ref "C47") (pin "2") (pinfunction "2_2") (pintype "passive"))
      (node (ref "C48") (pin "2") (pinfunction "2_2") (pintype "passive"))
      (node (ref "C55") (pin "2") (pinfunction "2_2") (pintype "passive"))
      (node (ref "C56") (pin "2") (pinfunction "2_2") (pintype "passive"))
      (node (ref "C57") (pin "2") (pinfunction "2_2") (pintype "passive"))
      (node (ref "C58") (pin "2") (pinfunction "2_2") (pintype "passive"))
      (node (ref "C59") (pin "1") (pinfunction "1_1") (pintype "passive"))
      (node (ref "C60") (pin "1") (pinfunction "1_1") (pintype "passive"))
      (node (ref "C68") (pin "1") (pinfunction "1_1") (pintype "passive"))
      (node (ref "C70") (pin "1") (pinfunction "1_1") (pintype "passive"))
      (node (ref "D13") (pin "1") (pinfunction "K_1") (pintype "passive"))
      (node (ref "J10") (pin "6") (pinfunction "Vss_6") (pintype "passive"))
      (node (ref "J10") (pin "9") (pinfunction "Shield_9") (pintype "passive"))
      (node (ref "J11") (pin "4") (pinfunction "ID_4") (pintype "power_in"))
      (node (ref "J11") (pin "5") (pinfunction "SHLD_5") (pintype "passive"))
      (node (ref "J20") (pin "14") (pinfunction "14_14") (pintype "passive"))
      (node (ref "J22") (pin "10") (pinfunction "10_10") (pintype "passive"))
      (node (ref "J22") (pin "12") (pinfunction "12_12") (pintype "passive"))
      (node (ref "J22") (pin "14") (pinfunction "14_14") (pintype "passive"))
      (node (ref "J22") (pin "16") (pinfunction "16_16") (pintype "passive"))
      (node (ref "J22") (pin "18") (pinfunction "18_18") (pintype "passive"))
      (node (ref "J22") (pin "20") (pinfunction "20_20") (pintype "passive"))
      (node (ref "J22") (pin "4") (pinfunction "4_4") (pintype "passive"))
      (node (ref "J22") (pin "6") (pinfunction "6_6") (pintype "passive"))
      (node (ref "J22") (pin "8") (pinfunction "8_8") (pintype "passive"))
      (node (ref "L6") (pin "1") (pinfunction "1_1") (pintype "passive"))
      (node (ref "L8") (pin "1") (pinfunction "1_1") (pintype "passive"))
      (node (ref "Q13") (pin "2") (pinfunction "S_2") (pintype "passive"))
      (node (ref "Q8") (pin "2") (pinfunction "S_2") (pintype "passive"))
      (node (ref "R100") (pin "1") (pinfunction "1_1") (pintype "passive"))
      (node (ref "R33") (pin "1") (pinfunction "1_1") (pintype "passive"))
      (node (ref "R83") (pin "1") (pinfunction "1_1") (pintype "passive"))
      (node (ref "S1") (pin "1") (pinfunction "1_1") (pintype "passive"))
      (node (ref "S1") (pin "2") (pinfunction "2_2") (pintype "passive"))
      (node (ref "S2") (pin "1") (pinfunction "1_1") (pintype "passive"))
      (node (ref "S2") (pin "2") (pinfunction "2_2") (pintype "passive"))
      (node (ref "U10") (pin "1") (pinfunction "GND_1") (pintype "power_in"))
      (node (ref "U5") (pin "24") (pinfunction "VSS_24") (pintype "input"))
      (node (ref "U5") (pin "33") (pinfunction "VSS_33") (pintype "input"))
      (node (ref "U5") (pin "43") (pinfunction "VSS_43") (pintype "input"))
      (node (ref "U5") (pin "57") (pinfunction "VSS_57") (pintype "input"))
      (node (ref "U5") (pin "66") (pinfunction "VSS_66") (pintype "input"))
      (node (ref "U5") (pin "78") (pinfunction "VSS_78") (pintype "input"))
    )
    (net (code "63") (name "GND_A") (class "Default")
      (node (ref "C53") (pin "1") (pinfunction "1_1") (pintype "passive"))
      (node (ref "C54") (pin "1") (pinfunction "1_1") (pintype "passive"))
      (node (ref "L8") (pin "2") (pinfunction "2_2") (pintype "passive"))
      (node (ref "U5") (pin "9") (pinfunction "VSSA_9") (pintype "input"))
    )
    (net (code "64") (name "Net-(C61-Pad1)") (class "Default")
      (node (ref "C61") (pin "1") (pinfunction "1_1") (pintype "passive"))
      (node (ref "R95") (pin "2") (pinfunction "2_2") (pintype "passive"))
    )
    (net (code "65") (name "Net-(D10-K)") (class "Default")
      (node (ref "D10") (pin "1") (pinfunction "K_1") (pintype "passive"))
      (node (ref "R93") (pin "2") (pinfunction "2_2") (pintype "passive"))
    )
    (net (code "66") (name "Net-(D12-K)") (class "Default")
      (node (ref "D12") (pin "1") (pinfunction "K_1") (pintype "passive"))
      (node (ref "L13") (pin "1") (pinfunction "1_1") (pintype "passive"))
      (node (ref "U6") (pin "1") (pinfunction "Out_1") (pintype "output"))
    )
    (net (code "67") (name "Net-(D13-A)") (class "Default")
      (node (ref "D13") (pin "2") (pinfunction "A_2") (pintype "passive"))
      (node (ref "R98") (pin "1") (pinfunction "1_1") (pintype "passive"))
    )
    (net (code "68") (name "Net-(D20-A)") (class "Default")
      (node (ref "C41") (pin "1") (pinfunction "1_1") (pintype "passive"))
      (node (ref "D20") (pin "2") (pinfunction "A_2") (pintype "passive"))
      (node (ref "J24") (pin "2") (pinfunction "2_2") (pintype "passive"))
      (node (ref "Q13") (pin "3") (pinfunction "D_3") (pintype "passive"))
    )
    (net (code "69") (name "Net-(J11-D+)") (class "Default")
      (node (ref "J11") (pin "3") (pinfunction "D+_3") (pintype "input"))
      (node (ref "R87") (pin "1") (pinfunction "1_1") (pintype "passive"))
      (node (ref "R91") (pin "1") (pinfunction "1_1") (pintype "passive"))
    )
    (net (code "70") (name "Net-(J11-D-)") (class "Default")
      (node (ref "J11") (pin "2") (pinfunction "D-_2") (pintype "input"))
      (node (ref "R90") (pin "1") (pinfunction "1_1") (pintype "passive"))
    )
    (net (code "71") (name "Net-(J11-VBUS)") (class "Default")
      (node (ref "J11") (pin "1") (pinfunction "VBUS_1") (pintype "power_in"))
      (node (ref "R89") (pin "1") (pinfunction "1_1") (pintype "passive"))
    )
    (net (code "72") (name "Net-(LS1-Pad1)") (class "Default")
      (node (ref "LS1") (pin "1") (pinfunction "1_1") (pintype "passive"))
      (node (ref "R84") (pin "2") (pinfunction "2_2") (pintype "passive"))
      (node (ref "R85") (pin "1") (pinfunction "1_1") (pintype "passive"))
    )
    (net (code "73") (name "Net-(Q7-D)") (class "Default")
      (node (ref "Q7") (pin "3") (pinfunction "D_3") (pintype "passive"))
      (node (ref "R87") (pin "2") (pinfunction "2_2") (pintype "passive"))
    )
    (net (code "74") (name "Net-(Q7-G)") (class "Default")
      (node (ref "Q7") (pin "1") (pinfunction "G_1") (pintype "passive"))
      (node (ref "R15") (pin "1") (pinfunction "1_1") (pintype "passive"))
      (node (ref "R76") (pin "1") (pinfunction "1_1") (pintype "passive"))
    )
    (net (code "75") (name "Net-(Q8-D)") (class "Default")
      (node (ref "LS1") (pin "2") (pinfunction "2_2") (pintype "passive"))
      (node (ref "Q8") (pin "3") (pinfunction "D_3") (pintype "passive"))
      (node (ref "R84") (pin "1") (pinfunction "1_1") (pintype "passive"))
    )
    (net (code "76") (name "Net-(Q8-G)") (class "Default")
      (node (ref "Q8") (pin "1") (pinfunction "G_1") (pintype "passive"))
      (node (ref "R100") (pin "2") (pinfunction "2_2") (pintype "passive"))
      (node (ref "R99") (pin "2") (pinfunction "2_2") (pintype "passive"))
    )
    (net (code "77") (name "Net-(Q13-G)") (class "Default")
      (node (ref "Q13") (pin "1") (pinfunction "G_1") (pintype "passive"))
      (node (ref "R11") (pin "2") (pinfunction "2_2") (pintype "passive"))
    )
    (net (code "78") (name "Net-(U5B-VREFN)") (class "Default")
      (node (ref "C50") (pin "1") (pinfunction "1_1") (pintype "passive"))
      (node (ref "C51") (pin "1") (pinfunction "1_1") (pintype "passive"))
      (node (ref "L6") (pin "2") (pinfunction "2_2") (pintype "passive"))
      (node (ref "U5") (pin "12") (pinfunction "VREFN_12") (pintype "input"))
    )
    (net (code "79") (name "Net-(U5B-VREFP)") (class "Default")
      (node (ref "C50") (pin "2") (pinfunction "2_2") (pintype "passive"))
      (node (ref "C51") (pin "2") (pinfunction "2_2") (pintype "passive"))
      (node (ref "L5") (pin "2") (pinfunction "2_2") (pintype "passive"))
      (node (ref "U5") (pin "10") (pinfunction "VREFP_10") (pintype "input"))
    )
    (net (code "80") (name "Net-(U5B-XTAL1)") (class "Default")
      (node (ref "C55") (pin "1") (pinfunction "1_1") (pintype "passive"))
      (node (ref "U5") (pin "19") (pinfunction "XTAL1_19") (pintype "input"))
      (node (ref "X2") (pin "3") (pinfunction "OSC2_3") (pintype "passive"))
    )
    (net (code "81") (name "Net-(U5B-XTAL2)") (class "Default")
      (node (ref "C56") (pin "1") (pinfunction "1_1") (pintype "passive"))
      (node (ref "U5") (pin "20") (pinfunction "XTAL2_20") (pintype "output"))
      (node (ref "X2") (pin "1") (pinfunction "OSC1_1") (pintype "passive"))
    )
    (net (code "82") (name "Net-(U6-Comp)") (class "Default")
      (node (ref "C61") (pin "2") (pinfunction "2_2") (pintype "passive"))
      (node (ref "C67") (pin "2") (pinfunction "2_2") (pintype "passive"))
      (node (ref "U6") (pin "4") (pinfunction "Comp_4") (pintype "passive"))
    )
    (net (code "83") (name "Net-(U6-FB)") (class "Default")
      (node (ref "R101") (pin "1") (pinfunction "1_1") (pintype "passive"))
      (node (ref "R102") (pin "2") (pinfunction "2_2") (pintype "passive"))
      (node (ref "U6") (pin "5") (pinfunction "FB_5") (pintype "input"))
    )
    (net (code "84") (name "Star_GND") (class "Default")
      (node (ref "C49") (pin "1") (pinfunction "1_1") (pintype "passive"))
      (node (ref "C63") (pin "1") (pinfunction "1_1") (pintype "passive"))
      (node (ref "C67") (pin "1") (pinfunction "1_1") (pintype "passive"))
      (node (ref "D12") (pin "2") (pinfunction "A_2") (pintype "passive"))
      (node (ref "J12") (pin "3") (pinfunction "3_3") (pintype "passive"))
      (node (ref "J12") (pin "4") (pinfunction "4_4") (pintype "passive"))
      (node (ref "R102") (pin "1") (pinfunction "1_1") (pintype "passive"))
      (node (ref "R95") (pin "1") (pinfunction "1_1") (pintype "passive"))
      (node (ref "U6") (pin "3") (pinfunction "Inh._3") (pintype "input"))
      (node (ref "U6") (pin "7") (pinfunction "GND_7") (pintype "power_in"))
    )
    (net (code "85") (name "V3.3") (class "Default")
      (node (ref "C43") (pin "2") (pinfunction "2_2") (pintype "passive"))
      (node (ref "C44") (pin "2") (pinfunction "2_2") (pintype "passive"))
      (node (ref "C45") (pin "1") (pinfunction "1_1") (pintype "passive"))
      (node (ref "C46") (pin "1") (pinfunction "1_1") (pintype "passive"))
      (node (ref "C47") (pin "1") (pinfunction "1_1") (pintype "passive"))
      (node (ref "C48") (pin "1") (pinfunction "1_1") (pintype "passive"))
      (node (ref "C57") (pin "1") (pinfunction "1_1") (pintype "passive"))
      (node (ref "C58") (pin "1") (pinfunction "1_1") (pintype "passive"))
      (node (ref "D10") (pin "2") (pinfunction "A_2") (pintype "passive"))
      (node (ref "D19") (pin "2") (pinfunction "A_2") (pintype "passive"))
      (node (ref "J10") (pin "4") (pinfunction "Vdd_4") (pintype "passive"))
      (node (ref "J20") (pin "2") (pinfunction "2_2") (pintype "passive"))
      (node (ref "J22") (pin "1") (pinfunction "1_1") (pintype "passive"))
      (node (ref "J22") (pin "2") (pinfunction "2_2") (pintype "passive"))
      (node (ref "L5") (pin "1") (pinfunction "1_1") (pintype "passive"))
      (node (ref "L7") (pin "1") (pinfunction "1_1") (pintype "passive"))
      (node (ref "Q7") (pin "2") (pinfunction "S_2") (pintype "passive"))
      (node (ref "R103") (pin "2") (pinfunction "2_2") (pintype "passive"))
      (node (ref "R115") (pin "1") (pinfunction "1_1") (pintype "passive"))
      (node (ref "R15") (pin "2") (pinfunction "2_2") (pintype "passive"))
      (node (ref "R72") (pin "1") (pinfunction "1_1") (pintype "passive"))
      (node (ref "R74") (pin "2") (pinfunction "2_2") (pintype "passive"))
      (node (ref "R75") (pin "1") (pinfunction "1_1") (pintype "passive"))
      (node (ref "R77") (pin "1") (pinfunction "1_1") (pintype "passive"))
      (node (ref "R85") (pin "2") (pinfunction "2_2") (pintype "passive"))
      (node (ref "R86") (pin "1") (pinfunction "1_1") (pintype "passive"))
      (node (ref "R98") (pin "2") (pinfunction "2_2") (pintype "passive"))
      (node (ref "U10") (pin "2") (pinfunction "OUT_2") (pintype "power_in"))
      (node (ref "U5") (pin "16") (pinfunction "VBAT_16") (pintype "input"))
      (node (ref "U5") (pin "21") (pinfunction "VDD(3V3)_21") (pintype "input"))
      (node (ref "U5") (pin "34") (pinfunction "VDD(REG)(3V3)_34") (pintype "input"))
      (node (ref "U5") (pin "42") (pinfunction "VDD(3V3)_42") (pintype "input"))
      (node (ref "U5") (pin "56") (pinfunction "VDD(3V3)_56") (pintype "input"))
      (node (ref "U5") (pin "67") (pinfunction "VDD(REG)(3V3)_67") (pintype "input"))
      (node (ref "U5") (pin "77") (pinfunction "VDD(3V3)_77") (pintype "input"))
    )
    (net (code "86") (name "V5") (class "Default")
      (node (ref "C63") (pin "2") (pinfunction "2_2") (pintype "passive"))
      (node (ref "D19") (pin "1") (pinfunction "K_1") (pintype "passive"))
      (node (ref "J18") (pin "15") (pinfunction "15_15") (pintype "passive"))
      (node (ref "L13") (pin "2") (pinfunction "2_2") (pintype "passive"))
      (node (ref "R101") (pin "2") (pinfunction "2_2") (pintype "passive"))
      (node (ref "U10") (pin "3") (pinfunction "IN_3") (pintype "power_in"))
    )
    (net (code "87") (name "VA3.3") (class "Default")
      (node (ref "C53") (pin "2") (pinfunction "2_2") (pintype "passive"))
      (node (ref "C54") (pin "2") (pinfunction "2_2") (pintype "passive"))
      (node (ref "L7") (pin "2") (pinfunction "2_2") (pintype "passive"))
      (node (ref "U5") (pin "8") (pinfunction "VDDA_8") (pintype "input"))
    )
    (net (code "88") (name "VMM") (class "Default")
      (node (ref "C41") (pin "2") (pinfunction "2_2") (pintype "passive"))
      (node (ref "C49") (pin "2") (pinfunction "2_2") (pintype "passive"))
      (node (ref "D20") (pin "1") (pinfunction "K_1") (pintype "passive"))
      (node (ref "J12") (pin "1") (pinfunction "1_1") (pintype "passive"))
      (node (ref "J12") (pin "2") (pinfunction "2_2") (pintype "passive"))
      (node (ref "J20") (pin "1") (pinfunction "1_1") (pintype "passive"))
      (node (ref "J24") (pin "1") (pinfunction "1_1") (pintype "passive"))
      (node (ref "U6") (pin "8") (pinfunction "Vcc_8") (pintype "power_in"))
    )
    (net (code "89") (name "unconnected-(J10-Data1-Pad8)") (class "Default")
      (node (ref "J10") (pin "8") (pinfunction "Data1_8") (pintype "passive+no_connect"))
    )
    (net (code "90") (name "unconnected-(J10-Data2-Pad1)") (class "Default")
      (node (ref "J10") (pin "1") (pinfunction "Data2_1") (pintype "passive+no_connect"))
    )
    (net (code "91") (name "unconnected-(J10-Shield-Pad10)") (class "Default")
      (node (ref "J10") (pin "10") (pinfunction "Shield_10") (pintype "passive+no_connect"))
    )
    (net (code "92") (name "unconnected-(J20-Pad15)") (class "Default")
      (node (ref "J20") (pin "15") (pinfunction "15_15") (pintype "passive+no_connect"))
    )
    (net (code "93") (name "unconnected-(J22-Pad11)") (class "Default")
      (node (ref "J22") (pin "11") (pinfunction "11_11") (pintype "passive"))
    )
    (net (code "94") (name "unconnected-(J22-Pad17)") (class "Default")
      (node (ref "J22") (pin "17") (pinfunction "17_17") (pintype "passive+no_connect"))
    )
    (net (code "95") (name "unconnected-(J22-Pad19)") (class "Default")
      (node (ref "J22") (pin "19") (pinfunction "19_19") (pintype "passive+no_connect"))
    )
    (net (code "96") (name "unconnected-(U5B-*RSTOUT-Pad11)") (class "Default")
      (node (ref "U5") (pin "11") (pinfunction "*RSTOUT_11") (pintype "output+no_connect"))
    )
    (net (code "97") (name "unconnected-(U5B-RTCX1-Pad13)") (class "Default")
      (node (ref "U5") (pin "13") (pinfunction "RTCX1_13") (pintype "input+no_connect"))
    )
    (net (code "98") (name "unconnected-(U5B-RTCX2-Pad15)") (class "Default")
      (node (ref "U5") (pin "15") (pinfunction "RTCX2_15") (pintype "output+no_connect"))
    )
    (net (code "99") (name "unconnected-(U6-Sync-Pad2)") (class "Default")
      (node (ref "U6") (pin "2") (pinfunction "Sync_2") (pintype "bidirectional+no_connect"))
    )
    (net (code "100") (name "unconnected-(U6-Vref-Pad6)") (class "Default")
      (node (ref "U6") (pin "6") (pinfunction "Vref_6") (pintype "output+no_connect"))
    )
  )
)
